# YOTSUBA_GNSS-receiver_MAX_ver_1_1.net
KiCad netlist of a schematic drawn in EAGLE
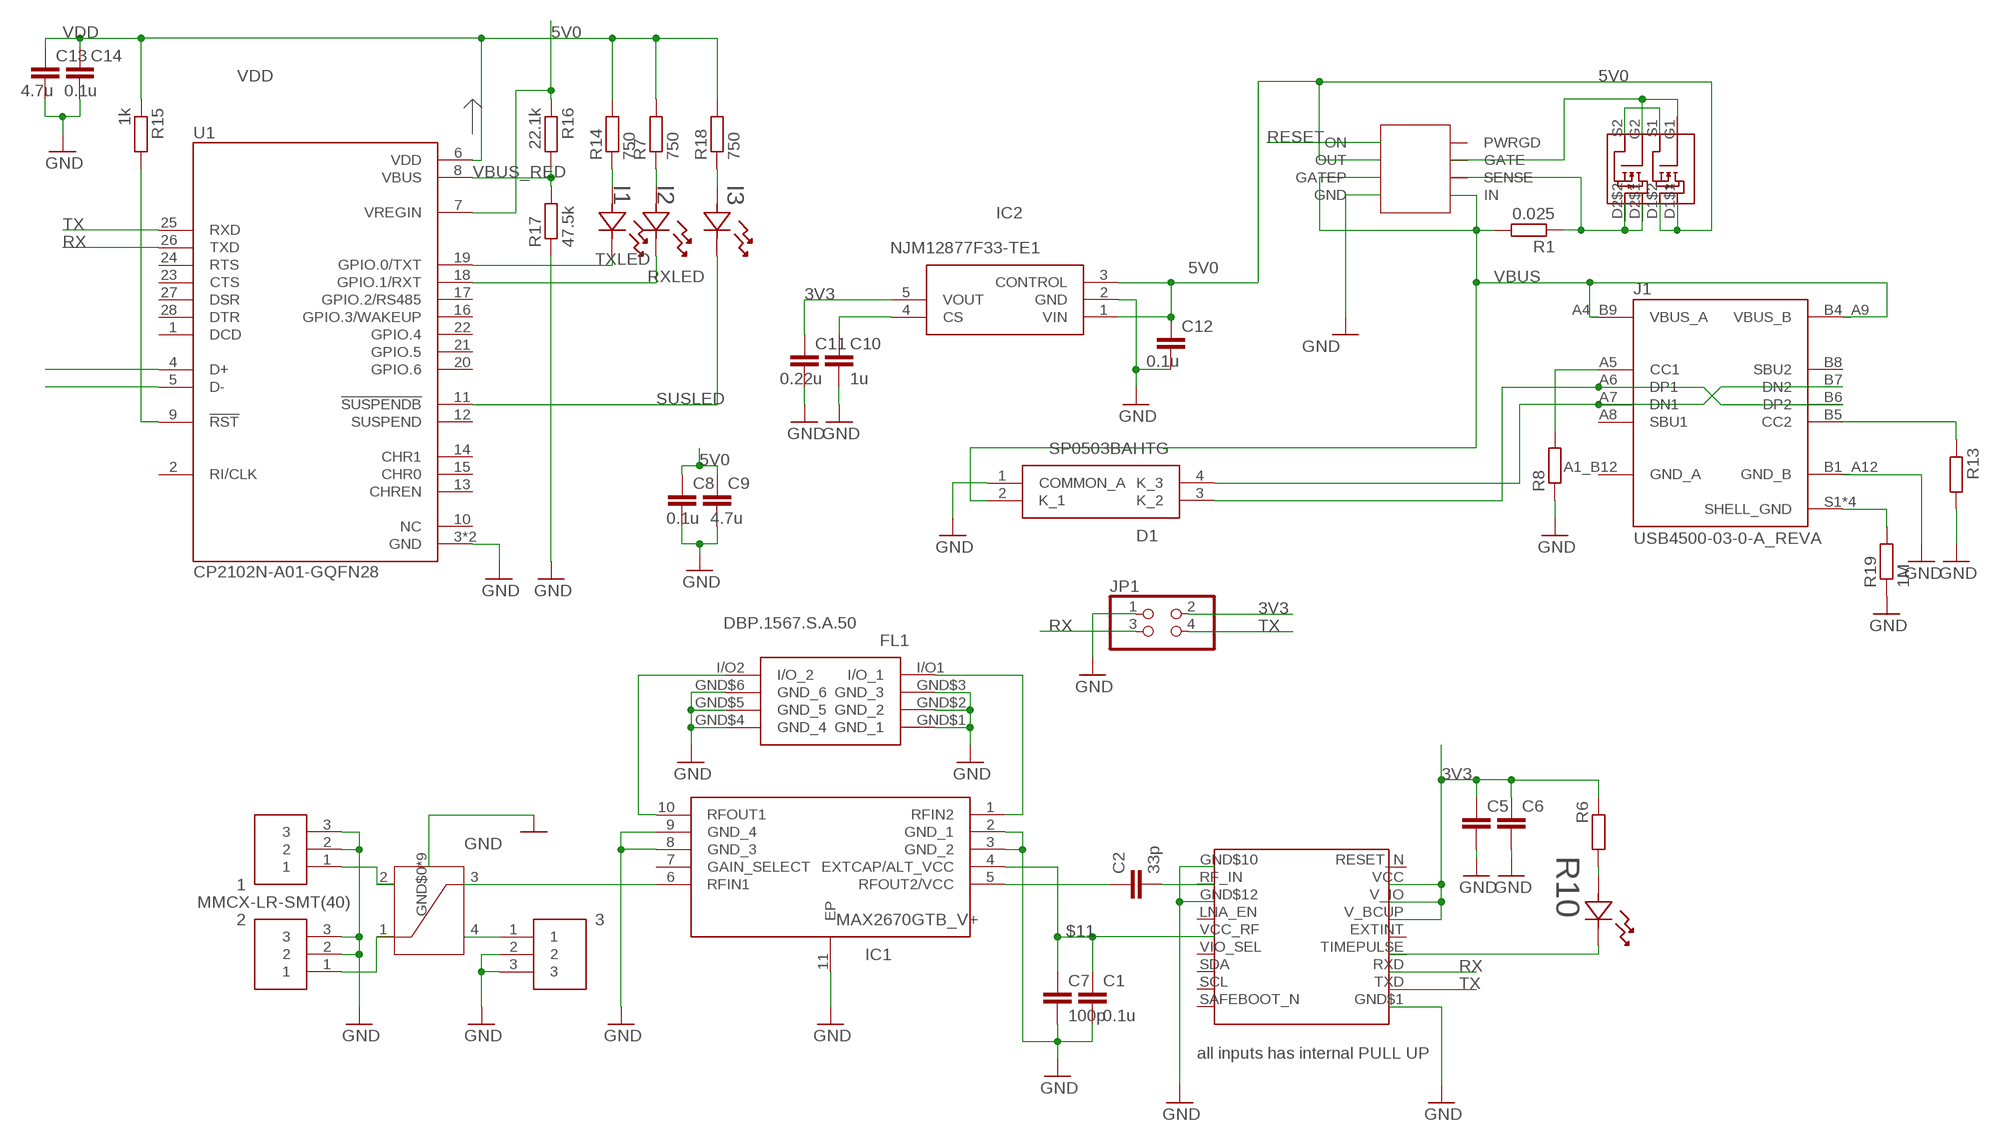
[diagram p0: schematic, sheet 1]

(export (version "E")
  (design (tool "Eeschema 10.0.6"))
  (components
    (comp (ref "1")
      (value "MMCX-LR-SMT(40)")
      (footprint "eagle-import:MMCX-LR-SMT(40)")
      (libsource (lib "eagle-import") (part "MMCX-LR-SMT(40)"))
    )
    (comp (ref "2")
      (value "MMCX-LR-SMT(40)")
      (footprint "eagle-import:MMCX-LR-SMT(40)")
      (libsource (lib "eagle-import") (part "MMCX-LR-SMT(40)"))
    )
    (comp (ref "3")
      (value "MMCX-LR-SMT(40)")
      (footprint "eagle-import:MMCX-LR-SMT(40)")
      (libsource (lib "eagle-import") (part "MMCX-LR-SMT(40)"))
    )
    (comp (ref "C1")
      (value "0.1u")
      (footprint "eagle-import:C1608")
      (libsource (lib "eagle-import") (part "C-EUC1608"))
    )
    (comp (ref "C2")
      (value "33p")
      (footprint "eagle-import:C1608")
      (libsource (lib "eagle-import") (part "C-EUC1608"))
    )
    (comp (ref "C5")
      (value "C-EUC1608")
      (footprint "eagle-import:C1608")
      (libsource (lib "eagle-import") (part "C-EUC1608"))
    )
    (comp (ref "C6")
      (value "C-EUC1608")
      (footprint "eagle-import:C1608")
      (libsource (lib "eagle-import") (part "C-EUC1608"))
    )
    (comp (ref "C7")
      (value "100p")
      (footprint "eagle-import:C1608")
      (libsource (lib "eagle-import") (part "C-EUC1608"))
    )
    (comp (ref "C8")
      (value "0.1u")
      (footprint "eagle-import:C1608")
      (libsource (lib "eagle-import") (part "C-EUC1608"))
    )
    (comp (ref "C9")
      (value "4.7u")
      (footprint "eagle-import:C1608")
      (libsource (lib "eagle-import") (part "C-EUC1608"))
    )
    (comp (ref "C10")
      (value "1u")
      (footprint "eagle-import:C1608")
      (libsource (lib "eagle-import") (part "C-EUC1608"))
    )
    (comp (ref "C11")
      (value "0.22u")
      (footprint "eagle-import:C1608")
      (libsource (lib "eagle-import") (part "C-EUC1608"))
    )
    (comp (ref "C12")
      (value "0.1u")
      (footprint "eagle-import:C1608")
      (libsource (lib "eagle-import") (part "C-EUC1608"))
    )
    (comp (ref "C13")
      (value "4.7u")
      (footprint "eagle-import:C1608")
      (libsource (lib "eagle-import") (part "C-EUC1608"))
    )
    (comp (ref "C14")
      (value "0.1u")
      (footprint "eagle-import:C1608")
      (libsource (lib "eagle-import") (part "C-EUC1608"))
    )
    (comp (ref "D1")
      (value "SP0503BAHTG")
      (footprint "eagle-import:SP0503BAHTG")
      (fields (field (name "MOUSER_PART_NUMBER") "576-SP0503BAHTG"))
      (libsource (lib "eagle-import") (part "SP0503BAHTG"))
    )
    (comp (ref "FL1")
      (value "DBP.1567.S.A.50")
      (footprint "eagle-import:DBP1567SA50")
      (libsource (lib "eagle-import") (part "DBP.1567.S.A.50"))
    )
    (comp (ref "I1")
      (value "SML-E12P8WT86")
      (footprint "eagle-import:LED_SMLD12_ROM")
      (fields (field (name "COPYRIGHT") "Copyright (C) 2023 Ultra Librarian. All rights reserved."))
      (libsource (lib "eagle-import") (part "SML-E12P8WT86"))
    )
    (comp (ref "I2")
      (value "SML-E12P8WT86")
      (footprint "eagle-import:LED_SMLD12_ROM")
      (fields (field (name "COPYRIGHT") "Copyright (C) 2023 Ultra Librarian. All rights reserved."))
      (libsource (lib "eagle-import") (part "SML-E12P8WT86"))
    )
    (comp (ref "I3")
      (value "SML-E12P8WT86")
      (footprint "eagle-import:LED_SMLD12_ROM")
      (fields (field (name "COPYRIGHT") "Copyright (C) 2023 Ultra Librarian. All rights reserved."))
      (libsource (lib "eagle-import") (part "SML-E12P8WT86"))
    )
    (comp (ref "IC1")
      (value "MAX2670GTB_V+")
      (footprint "eagle-import:SON50P300X300X80-11N")
      (fields
        (field (name "MANUFACTURER_PART_NUMBER") "MAX2670GTB/V+")
        (field (name "MOUSER_PART_NUMBER") "700-MAX2670GTB/V+")
      )
      (libsource (lib "eagle-import") (part "MAX2670GTB_V+"))
    )
    (comp (ref "IC2")
      (value "NJM12877F33-TE1")
      (footprint "eagle-import:SOT95P280X120-5N")
      (fields (field (name "MOUSER_PART_NUMBER") "513-NJM12877F33-TE1"))
      (libsource (lib "eagle-import") (part "NJM12877F33-TE1"))
    )
    (comp (ref "J1")
      (value "USB4500-03-0-A_REVA")
      (footprint "eagle-import:GCT_USB4500-03-0-A_REVA")
      (fields
        (field (name "DIGI-KEY_PART_NUMBER") "2073-USB4500-03-0-ATR-ND")
        (field (name "MF") "Global Connector Technology")
        (field (name "MP") "USB4500-03-0-A")
      )
      (libsource (lib "eagle-import") (part "USB4500-03-0-A_REVA"))
    )
    (comp (ref "JP1")
      (value "PINHD-2X2")
      (footprint "eagle-import:2X02")
      (libsource (lib "eagle-import") (part "PINHD-2X2"))
    )
    (comp (ref "R1")
      (value "0.025")
      (footprint "eagle-import:R0603")
      (libsource (lib "eagle-import") (part "R-EU_R0603"))
    )
    (comp (ref "R6")
      (value "R-EU_R0603")
      (footprint "eagle-import:R0603")
      (libsource (lib "eagle-import") (part "R-EU_R0603"))
    )
    (comp (ref "R7")
      (value "750")
      (footprint "eagle-import:R0603")
      (libsource (lib "eagle-import") (part "R-EU_R0603"))
    )
    (comp (ref "R8")
      (value "R-EU_R0603")
      (footprint "eagle-import:R0603")
      (libsource (lib "eagle-import") (part "R-EU_R0603"))
    )
    (comp (ref "R10")
      (value "SML-E12P8WT86")
      (footprint "eagle-import:LED_SMLD12_ROM")
      (fields (field (name "COPYRIGHT") "Copyright (C) 2023 Ultra Librarian. All rights reserved."))
      (libsource (lib "eagle-import") (part "SML-E12P8WT86"))
    )
    (comp (ref "R13")
      (value "R-EU_R0603")
      (footprint "eagle-import:R0603")
      (libsource (lib "eagle-import") (part "R-EU_R0603"))
    )
    (comp (ref "R14")
      (value "750")
      (footprint "eagle-import:R0603")
      (libsource (lib "eagle-import") (part "R-EU_R0603"))
    )
    (comp (ref "R15")
      (value "1k")
      (footprint "eagle-import:R0603")
      (libsource (lib "eagle-import") (part "R-EU_R0603"))
    )
    (comp (ref "R16")
      (value "22.1k")
      (footprint "eagle-import:R0603")
      (libsource (lib "eagle-import") (part "R-EU_R0603"))
    )
    (comp (ref "R17")
      (value "47.5k")
      (footprint "eagle-import:R0603")
      (libsource (lib "eagle-import") (part "R-EU_R0603"))
    )
    (comp (ref "R18")
      (value "750")
      (footprint "eagle-import:R0603")
      (libsource (lib "eagle-import") (part "R-EU_R0603"))
    )
    (comp (ref "R19")
      (value "1M")
      (footprint "eagle-import:R0603")
      (libsource (lib "eagle-import") (part "R-EU_R0603"))
    )
    (comp (ref "U$1")
      (value "MAX_M10S")
      (footprint "eagle-import:MAX-M10S")
      (libsource (lib "eagle-import") (part "MAX_M10S"))
    )
    (comp (ref "U$3")
      (value "HC125.A")
      (footprint "eagle-import:HC125.A")
      (libsource (lib "eagle-import") (part "HC125.A"))
    )
    (comp (ref "U$7")
      (value "DMG6898LSD")
      (footprint "eagle-import:SOIC127P600X150-8N")
      (libsource (lib "eagle-import") (part "DMG6898LSD"))
    )
    (comp (ref "U$8")
      (value "LTC4361")
      (footprint "eagle-import:SOP65P280X100-8N")
      (libsource (lib "eagle-import") (part "LTC4361"))
    )
    (comp (ref "U1")
      (value "CP2102N-A01-GQFN28")
      (footprint "eagle-import:QFN50P500X500X80-29N")
      (fields (field (name "MF") "Silicon Labs"))
      (libsource (lib "eagle-import") (part "CP2102N-A01-GQFN28"))
    )
  )
  (nets
    (net (code "1") (name "/$11") (class "Default")
      (node (ref "C1") (pin "1") (pinfunction "1_1") (pintype "passive"))
      (node (ref "C7") (pin "1") (pinfunction "1_1") (pintype "passive"))
      (node (ref "IC1") (pin "4") (pinfunction "EXTCAP/ALT_VCC_4") (pintype "bidirectional"))
      (node (ref "U$1") (pin "VCC_RF") (pinfunction "VCC_RF_VCC_RF") (pintype "bidirectional"))
    )
    (net (code "2") (name "/3V3") (class "Default")
      (node (ref "C11") (pin "1") (pinfunction "1_1") (pintype "passive"))
      (node (ref "C5") (pin "1") (pinfunction "1_1") (pintype "passive"))
      (node (ref "C6") (pin "1") (pinfunction "1_1") (pintype "passive"))
      (node (ref "IC2") (pin "5") (pinfunction "VOUT_5") (pintype "bidirectional"))
      (node (ref "JP1") (pin "2") (pinfunction "2_2") (pintype "passive"))
      (node (ref "R6") (pin "2") (pinfunction "2_2") (pintype "passive"))
      (node (ref "U$1") (pin "VCC") (pinfunction "VCC_VCC") (pintype "bidirectional"))
      (node (ref "U$1") (pin "V_BCUP") (pinfunction "V_BCKP_V_BCUP") (pintype "bidirectional"))
      (node (ref "U$1") (pin "V_IO") (pinfunction "V_IO_V_IO") (pintype "bidirectional"))
    )
    (net (code "3") (name "/5V0") (class "Default")
      (node (ref "C12") (pin "1") (pinfunction "1_1") (pintype "passive"))
      (node (ref "C8") (pin "1") (pinfunction "1_1") (pintype "passive"))
      (node (ref "C9") (pin "1") (pinfunction "1_1") (pintype "passive"))
      (node (ref "IC2") (pin "1") (pinfunction "VIN_1") (pintype "bidirectional"))
      (node (ref "IC2") (pin "3") (pinfunction "CONTROL_3") (pintype "bidirectional"))
      (node (ref "R16") (pin "1") (pinfunction "1_1") (pintype "passive"))
      (node (ref "U$7") (pin "D1$1") (pinfunction "D1$1_D1$1") (pintype "bidirectional"))
      (node (ref "U$7") (pin "D1$2") (pinfunction "D1$2_D1$2") (pintype "bidirectional"))
      (node (ref "U$8") (pin "OUT") (pinfunction "OUT_OUT") (pintype "bidirectional"))
      (node (ref "U1") (pin "7") (pinfunction "VREGIN_7") (pintype "power_in"))
    )
    (net (code "4") (name "/D+") (class "Default")
      (node (ref "D1") (pin "3") (pinfunction "K_2_3") (pintype "bidirectional"))
      (node (ref "J1") (pin "A6") (pinfunction "DP1_A6") (pintype "bidirectional"))
      (node (ref "J1") (pin "B6") (pinfunction "DP2_B6") (pintype "bidirectional"))
      (node (ref "U1") (pin "4") (pinfunction "D+_4") (pintype "bidirectional"))
    )
    (net (code "5") (name "/D-") (class "Default")
      (node (ref "D1") (pin "4") (pinfunction "K_3_4") (pintype "bidirectional"))
      (node (ref "J1") (pin "A7") (pinfunction "DN1_A7") (pintype "bidirectional"))
      (node (ref "J1") (pin "B7") (pinfunction "DN2_B7") (pintype "bidirectional"))
      (node (ref "U1") (pin "5") (pinfunction "D-_5") (pintype "bidirectional"))
    )
    (net (code "6") (name "/GND_A") (class "Default")
      (node (ref "J1") (pin "A1_B12") (pinfunction "GND_A_A1_B12") (pintype "power_in"))
    )
    (net (code "7") (name "/RESET") (class "Default")
      (node (ref "U$8") (pin "ON") (pinfunction "ON_ON") (pintype "bidirectional"))
    )
    (net (code "8") (name "/RX") (class "Default")
      (node (ref "JP1") (pin "3") (pinfunction "3_3") (pintype "passive"))
      (node (ref "U$1") (pin "RXD") (pinfunction "RXD_RXD") (pintype "bidirectional"))
      (node (ref "U1") (pin "26") (pinfunction "TXD_26") (pintype "output"))
    )
    (net (code "9") (name "/RXLED") (class "Default")
      (node (ref "I2") (pin "1") (pinfunction "1_1") (pintype "passive"))
      (node (ref "U1") (pin "18") (pinfunction "GPIO.1/RXT_18") (pintype "bidirectional"))
    )
    (net (code "10") (name "/SUSLED") (class "Default")
      (node (ref "I3") (pin "1") (pinfunction "1_1") (pintype "passive"))
      (node (ref "U1") (pin "11") (pinfunction "~{SUSPENDB}_11") (pintype "output"))
    )
    (net (code "11") (name "/TX") (class "Default")
      (node (ref "JP1") (pin "4") (pinfunction "4_4") (pintype "passive"))
      (node (ref "U$1") (pin "TXD") (pinfunction "TXD_TXD") (pintype "bidirectional"))
      (node (ref "U1") (pin "25") (pinfunction "RXD_25") (pintype "input"))
    )
    (net (code "12") (name "/TXLED") (class "Default")
      (node (ref "I1") (pin "1") (pinfunction "1_1") (pintype "passive"))
      (node (ref "U1") (pin "19") (pinfunction "GPIO.0/TXT_19") (pintype "bidirectional"))
    )
    (net (code "13") (name "/VBUS") (class "Default")
      (node (ref "D1") (pin "2") (pinfunction "K_1_2") (pintype "bidirectional"))
      (node (ref "J1") (pin "A4_B9") (pinfunction "VBUS_A_A4_B9") (pintype "power_in"))
      (node (ref "J1") (pin "B4_A9") (pinfunction "VBUS_B_B4_A9") (pintype "power_in"))
      (node (ref "R1") (pin "2") (pinfunction "2_2") (pintype "passive"))
      (node (ref "U$8") (pin "GATEP") (pinfunction "GATEP_GATEP") (pintype "bidirectional"))
      (node (ref "U$8") (pin "IN") (pinfunction "IN_IN") (pintype "bidirectional"))
    )
    (net (code "14") (name "/VBUS_RED") (class "Default")
      (node (ref "R16") (pin "2") (pinfunction "2_2") (pintype "passive"))
      (node (ref "R17") (pin "2") (pinfunction "2_2") (pintype "passive"))
      (node (ref "U1") (pin "8") (pinfunction "VBUS_8") (pintype "power_in"))
    )
    (net (code "15") (name "/VDD") (class "Default")
      (node (ref "C13") (pin "1") (pinfunction "1_1") (pintype "passive"))
      (node (ref "C14") (pin "1") (pinfunction "1_1") (pintype "passive"))
      (node (ref "R14") (pin "2") (pinfunction "2_2") (pintype "passive"))
      (node (ref "R15") (pin "1") (pinfunction "1_1") (pintype "passive"))
      (node (ref "R18") (pin "2") (pinfunction "2_2") (pintype "passive"))
      (node (ref "R7") (pin "2") (pinfunction "2_2") (pintype "passive"))
      (node (ref "U1") (pin "6") (pinfunction "VDD_6") (pintype "power_in"))
    )
    (net (code "16") (name "GND") (class "Default")
      (node (ref "1") (pin "2") (pinfunction "2_2") (pintype "bidirectional"))
      (node (ref "1") (pin "3") (pinfunction "3_3") (pintype "bidirectional"))
      (node (ref "2") (pin "2") (pinfunction "2_2") (pintype "bidirectional"))
      (node (ref "2") (pin "3") (pinfunction "3_3") (pintype "bidirectional"))
      (node (ref "3") (pin "2") (pinfunction "2_2") (pintype "bidirectional"))
      (node (ref "3") (pin "3") (pinfunction "3_3") (pintype "bidirectional"))
      (node (ref "C1") (pin "2") (pinfunction "2_2") (pintype "passive"))
      (node (ref "C10") (pin "2") (pinfunction "2_2") (pintype "passive"))
      (node (ref "C11") (pin "2") (pinfunction "2_2") (pintype "passive"))
      (node (ref "C12") (pin "2") (pinfunction "2_2") (pintype "passive"))
      (node (ref "C13") (pin "2") (pinfunction "2_2") (pintype "passive"))
      (node (ref "C14") (pin "2") (pinfunction "2_2") (pintype "passive"))
      (node (ref "C5") (pin "2") (pinfunction "2_2") (pintype "passive"))
      (node (ref "C6") (pin "2") (pinfunction "2_2") (pintype "passive"))
      (node (ref "C7") (pin "2") (pinfunction "2_2") (pintype "passive"))
      (node (ref "C8") (pin "2") (pinfunction "2_2") (pintype "passive"))
      (node (ref "C9") (pin "2") (pinfunction "2_2") (pintype "passive"))
      (node (ref "D1") (pin "1") (pinfunction "COMMON_A_1") (pintype "bidirectional"))
      (node (ref "FL1") (pin "GND$1") (pinfunction "GND_1_GND$1") (pintype "bidirectional"))
      (node (ref "FL1") (pin "GND$2") (pinfunction "GND_2_GND$2") (pintype "bidirectional"))
      (node (ref "FL1") (pin "GND$3") (pinfunction "GND_3_GND$3") (pintype "bidirectional"))
      (node (ref "FL1") (pin "GND$4") (pinfunction "GND_4_GND$4") (pintype "bidirectional"))
      (node (ref "FL1") (pin "GND$5") (pinfunction "GND_5_GND$5") (pintype "bidirectional"))
      (node (ref "FL1") (pin "GND$6") (pinfunction "GND_6_GND$6") (pintype "bidirectional"))
      (node (ref "IC1") (pin "11") (pinfunction "EP_11") (pintype "bidirectional"))
      (node (ref "IC1") (pin "2") (pinfunction "GND_1_2") (pintype "bidirectional"))
      (node (ref "IC1") (pin "3") (pinfunction "GND_2_3") (pintype "bidirectional"))
      (node (ref "IC1") (pin "8") (pinfunction "GND_3_8") (pintype "bidirectional"))
      (node (ref "IC1") (pin "9") (pinfunction "GND_4_9") (pintype "bidirectional"))
      (node (ref "IC2") (pin "2") (pinfunction "GND_2") (pintype "bidirectional"))
      (node (ref "J1") (pin "B1_A12") (pinfunction "GND_B_B1_A12") (pintype "power_in"))
      (node (ref "JP1") (pin "1") (pinfunction "1_1") (pintype "passive"))
      (node (ref "R13") (pin "2") (pinfunction "2_2") (pintype "passive"))
      (node (ref "R17") (pin "1") (pinfunction "1_1") (pintype "passive"))
      (node (ref "R19") (pin "1") (pinfunction "1_1") (pintype "passive"))
      (node (ref "R8") (pin "1") (pinfunction "1_1") (pintype "passive"))
      (node (ref "U$1") (pin "GND$1") (pinfunction "GND$1_GND$1") (pintype "bidirectional"))
      (node (ref "U$1") (pin "GND$10") (pinfunction "GND$10_GND$10") (pintype "bidirectional"))
      (node (ref "U$1") (pin "GND$12") (pinfunction "GND$12_GND$12") (pintype "bidirectional"))
      (node (ref "U$3") (pin "GND$0") (pinfunction "GND_GND$0") (pintype "bidirectional"))
      (node (ref "U$3") (pin "GND$1") (pinfunction "GND_GND$1") (pintype "bidirectional"))
      (node (ref "U$3") (pin "GND$2") (pinfunction "GND_GND$2") (pintype "bidirectional"))
      (node (ref "U$3") (pin "GND$3") (pinfunction "GND_GND$3") (pintype "bidirectional"))
      (node (ref "U$3") (pin "GND$4") (pinfunction "GND_GND$4") (pintype "bidirectional"))
      (node (ref "U$3") (pin "GND$5") (pinfunction "GND_GND$5") (pintype "bidirectional"))
      (node (ref "U$3") (pin "GND$6") (pinfunction "GND_GND$6") (pintype "bidirectional"))
      (node (ref "U$3") (pin "GND$7") (pinfunction "GND_GND$7") (pintype "bidirectional"))
      (node (ref "U$3") (pin "GND$8") (pinfunction "GND_GND$8") (pintype "bidirectional"))
      (node (ref "U$8") (pin "GND") (pinfunction "GND_GND") (pintype "bidirectional"))
      (node (ref "U1") (pin "29") (pinfunction "GND_29") (pintype "power_in"))
      (node (ref "U1") (pin "3") (pinfunction "GND_3") (pintype "power_in"))
    )
    (net (code "17") (name "Net-(1-Pad1)") (class "Default")
      (node (ref "1") (pin "1") (pinfunction "1_1") (pintype "bidirectional"))
      (node (ref "U$3") (pin "2") (pinfunction "2_2") (pintype "bidirectional"))
    )
    (net (code "18") (name "Net-(2-Pad1)") (class "Default")
      (node (ref "2") (pin "1") (pinfunction "1_1") (pintype "bidirectional"))
      (node (ref "U$3") (pin "1") (pinfunction "1_1") (pintype "bidirectional"))
    )
    (net (code "19") (name "Net-(3-Pad1)") (class "Default")
      (node (ref "3") (pin "1") (pinfunction "1_1") (pintype "bidirectional"))
      (node (ref "U$3") (pin "4") (pinfunction "4_4") (pintype "bidirectional"))
    )
    (net (code "20") (name "Net-(C2-Pad2)") (class "Default")
      (node (ref "C2") (pin "2") (pinfunction "2_2") (pintype "passive"))
      (node (ref "U$1") (pin "RF_IN") (pinfunction "RF_IN_RF_IN") (pintype "bidirectional"))
    )
    (net (code "21") (name "Net-(FL1-I{slash}O_1)") (class "Default")
      (node (ref "FL1") (pin "I/O1") (pinfunction "I/O_1_I/O1") (pintype "bidirectional"))
      (node (ref "IC1") (pin "1") (pinfunction "RFIN2_1") (pintype "bidirectional"))
    )
    (net (code "22") (name "Net-(FL1-I{slash}O_2)") (class "Default")
      (node (ref "FL1") (pin "I/O2") (pinfunction "I/O_2_I/O2") (pintype "bidirectional"))
      (node (ref "IC1") (pin "10") (pinfunction "RFOUT1_10") (pintype "bidirectional"))
    )
    (net (code "23") (name "Net-(I1-Pad2)") (class "Default")
      (node (ref "I1") (pin "2") (pinfunction "2_2") (pintype "passive"))
      (node (ref "R14") (pin "1") (pinfunction "1_1") (pintype "passive"))
    )
    (net (code "24") (name "Net-(I2-Pad2)") (class "Default")
      (node (ref "I2") (pin "2") (pinfunction "2_2") (pintype "passive"))
      (node (ref "R7") (pin "1") (pinfunction "1_1") (pintype "passive"))
    )
    (net (code "25") (name "Net-(I3-Pad2)") (class "Default")
      (node (ref "I3") (pin "2") (pinfunction "2_2") (pintype "passive"))
      (node (ref "R18") (pin "1") (pinfunction "1_1") (pintype "passive"))
    )
    (net (code "26") (name "Net-(IC1-RFIN1)") (class "Default")
      (node (ref "IC1") (pin "6") (pinfunction "RFIN1_6") (pintype "bidirectional"))
      (node (ref "U$3") (pin "3") (pinfunction "3_3") (pintype "bidirectional"))
    )
    (net (code "27") (name "Net-(IC1-RFOUT2{slash}VCC)") (class "Default")
      (node (ref "C2") (pin "1") (pinfunction "1_1") (pintype "passive"))
      (node (ref "IC1") (pin "5") (pinfunction "RFOUT2/VCC_5") (pintype "bidirectional"))
    )
    (net (code "28") (name "Net-(IC2-CS)") (class "Default")
      (node (ref "C10") (pin "1") (pinfunction "1_1") (pintype "passive"))
      (node (ref "IC2") (pin "4") (pinfunction "CS_4") (pintype "bidirectional"))
    )
    (net (code "29") (name "Net-(J1-CC1)") (class "Default")
      (node (ref "J1") (pin "A5") (pinfunction "CC1_A5") (pintype "bidirectional"))
      (node (ref "R8") (pin "2") (pinfunction "2_2") (pintype "passive"))
    )
    (net (code "30") (name "Net-(J1-CC2)") (class "Default")
      (node (ref "J1") (pin "B5") (pinfunction "CC2_B5") (pintype "bidirectional"))
      (node (ref "R13") (pin "1") (pinfunction "1_1") (pintype "passive"))
    )
    (net (code "31") (name "Net-(J1-SHELL_GND-PadS1)") (class "Default")
      (node (ref "J1") (pin "S1") (pinfunction "SHELL_GND_S1") (pintype "power_in"))
      (node (ref "J1") (pin "S2") (pinfunction "SHELL_GND_S2") (pintype "power_in"))
      (node (ref "J1") (pin "S3") (pinfunction "SHELL_GND_S3") (pintype "power_in"))
      (node (ref "J1") (pin "S4") (pinfunction "SHELL_GND_S4") (pintype "power_in"))
      (node (ref "R19") (pin "2") (pinfunction "2_2") (pintype "passive"))
    )
    (net (code "32") (name "Net-(R1-Pad1)") (class "Default")
      (node (ref "R1") (pin "1") (pinfunction "1_1") (pintype "passive"))
      (node (ref "U$7") (pin "D2$1") (pinfunction "D2$1_D2$1") (pintype "bidirectional"))
      (node (ref "U$7") (pin "D2$2") (pinfunction "D2$2_D2$2") (pintype "bidirectional"))
      (node (ref "U$8") (pin "SENSE") (pinfunction "SENSE_SENSE") (pintype "bidirectional"))
    )
    (net (code "33") (name "Net-(R10-Pad1)") (class "Default")
      (node (ref "R10") (pin "1") (pinfunction "1_1") (pintype "passive"))
      (node (ref "U$1") (pin "TIMEPULSE") (pinfunction "TIMEPULSE_TIMEPULSE") (pintype "bidirectional"))
    )
    (net (code "34") (name "Net-(R10-Pad2)") (class "Default")
      (node (ref "R10") (pin "2") (pinfunction "2_2") (pintype "passive"))
      (node (ref "R6") (pin "1") (pinfunction "1_1") (pintype "passive"))
    )
    (net (code "35") (name "Net-(U$7-PadG1)") (class "Default")
      (node (ref "U$7") (pin "G1") (pinfunction "G1_G1") (pintype "bidirectional"))
      (node (ref "U$7") (pin "G2") (pinfunction "G2_G2") (pintype "bidirectional"))
      (node (ref "U$8") (pin "GATE") (pinfunction "GATE_GATE") (pintype "bidirectional"))
    )
    (net (code "36") (name "Net-(U$7-PadS1)") (class "Default")
      (node (ref "U$7") (pin "S1") (pinfunction "S1_S1") (pintype "bidirectional"))
      (node (ref "U$7") (pin "S2") (pinfunction "S2_S2") (pintype "bidirectional"))
    )
    (net (code "37") (name "Net-(U1-~{RST})") (class "Default")
      (node (ref "R15") (pin "2") (pinfunction "2_2") (pintype "passive"))
      (node (ref "U1") (pin "9") (pinfunction "~{RST}_9") (pintype "input"))
    )
    (net (code "38") (name "unconnected-(IC1-GAIN_SELECT-Pad7)") (class "Default")
      (node (ref "IC1") (pin "7") (pinfunction "GAIN_SELECT_7") (pintype "bidirectional"))
    )
    (net (code "39") (name "unconnected-(J1-SBU1-PadA8)") (class "Default")
      (node (ref "J1") (pin "A8") (pinfunction "SBU1_A8") (pintype "bidirectional"))
    )
    (net (code "40") (name "unconnected-(J1-SBU2-PadB8)") (class "Default")
      (node (ref "J1") (pin "B8") (pinfunction "SBU2_B8") (pintype "bidirectional"))
    )
    (net (code "41") (name "unconnected-(U$1-PadEXTINT)") (class "Default")
      (node (ref "U$1") (pin "EXTINT") (pinfunction "EXTINT_EXTINT") (pintype "bidirectional"))
    )
    (net (code "42") (name "unconnected-(U$1-PadLNA_EN)") (class "Default")
      (node (ref "U$1") (pin "LNA_EN") (pinfunction "LNA_EN_LNA_EN") (pintype "bidirectional"))
    )
    (net (code "43") (name "unconnected-(U$1-PadRESET_N)") (class "Default")
      (node (ref "U$1") (pin "RESET_N") (pinfunction "RESET_N_RESET_N") (pintype "bidirectional"))
    )
    (net (code "44") (name "unconnected-(U$1-PadSAFEBOOT_N)") (class "Default")
      (node (ref "U$1") (pin "SAFEBOOT_N") (pinfunction "SAFEBOOT_N_SAFEBOOT_N") (pintype "bidirectional"))
    )
    (net (code "45") (name "unconnected-(U$1-PadSCL)") (class "Default")
      (node (ref "U$1") (pin "SCL") (pinfunction "SCL_SCL") (pintype "bidirectional"))
    )
    (net (code "46") (name "unconnected-(U$1-PadSDA)") (class "Default")
      (node (ref "U$1") (pin "SDA") (pinfunction "SDA_SDA") (pintype "bidirectional"))
    )
    (net (code "47") (name "unconnected-(U$1-PadVIO_SEL)") (class "Default")
      (node (ref "U$1") (pin "VIO_SEL") (pinfunction "VIO_SEL_VIO_SEL") (pintype "bidirectional"))
    )
    (net (code "48") (name "unconnected-(U$8-PadPWRGD)") (class "Default")
      (node (ref "U$8") (pin "PWRGD") (pinfunction "PWRGD_PWRGD") (pintype "bidirectional"))
    )
    (net (code "49") (name "unconnected-(U1-CHR0-Pad15)") (class "Default")
      (node (ref "U1") (pin "15") (pinfunction "CHR0_15") (pintype "output"))
    )
    (net (code "50") (name "unconnected-(U1-CHR1-Pad14)") (class "Default")
      (node (ref "U1") (pin "14") (pinfunction "CHR1_14") (pintype "output"))
    )
    (net (code "51") (name "unconnected-(U1-CHREN-Pad13)") (class "Default")
      (node (ref "U1") (pin "13") (pinfunction "CHREN_13") (pintype "output"))
    )
    (net (code "52") (name "unconnected-(U1-CTS-Pad23)") (class "Default")
      (node (ref "U1") (pin "23") (pinfunction "CTS_23") (pintype "input"))
    )
    (net (code "53") (name "unconnected-(U1-DCD-Pad1)") (class "Default")
      (node (ref "U1") (pin "1") (pinfunction "DCD_1") (pintype "input"))
    )
    (net (code "54") (name "unconnected-(U1-DSR-Pad27)") (class "Default")
      (node (ref "U1") (pin "27") (pinfunction "DSR_27") (pintype "input"))
    )
    (net (code "55") (name "unconnected-(U1-DTR-Pad28)") (class "Default")
      (node (ref "U1") (pin "28") (pinfunction "DTR_28") (pintype "output"))
    )
    (net (code "56") (name "unconnected-(U1-GPIO.2{slash}RS485-Pad17)") (class "Default")
      (node (ref "U1") (pin "17") (pinfunction "GPIO.2/RS485_17") (pintype "bidirectional"))
    )
    (net (code "57") (name "unconnected-(U1-GPIO.3{slash}WAKEUP-Pad16)") (class "Default")
      (node (ref "U1") (pin "16") (pinfunction "GPIO.3/WAKEUP_16") (pintype "bidirectional"))
    )
    (net (code "58") (name "unconnected-(U1-GPIO.4-Pad22)") (class "Default")
      (node (ref "U1") (pin "22") (pinfunction "GPIO.4_22") (pintype "bidirectional"))
    )
    (net (code "59") (name "unconnected-(U1-GPIO.5-Pad21)") (class "Default")
      (node (ref "U1") (pin "21") (pinfunction "GPIO.5_21") (pintype "bidirectional"))
    )
    (net (code "60") (name "unconnected-(U1-GPIO.6-Pad20)") (class "Default")
      (node (ref "U1") (pin "20") (pinfunction "GPIO.6_20") (pintype "bidirectional"))
    )
    (net (code "61") (name "unconnected-(U1-NC-Pad10)") (class "Default")
      (node (ref "U1") (pin "10") (pinfunction "NC_10") (pintype "no_connect"))
    )
    (net (code "62") (name "unconnected-(U1-RI{slash}CLK-Pad2)") (class "Default")
      (node (ref "U1") (pin "2") (pinfunction "RI/CLK_2") (pintype "bidirectional"))
    )
    (net (code "63") (name "unconnected-(U1-RTS-Pad24)") (class "Default")
      (node (ref "U1") (pin "24") (pinfunction "RTS_24") (pintype "output"))
    )
    (net (code "64") (name "unconnected-(U1-SUSPEND-Pad12)") (class "Default")
      (node (ref "U1") (pin "12") (pinfunction "SUSPEND_12") (pintype "output"))
    )
  )
)
